# CANBus.net
KiCad netlist of a schematic drawn in Altium Designer
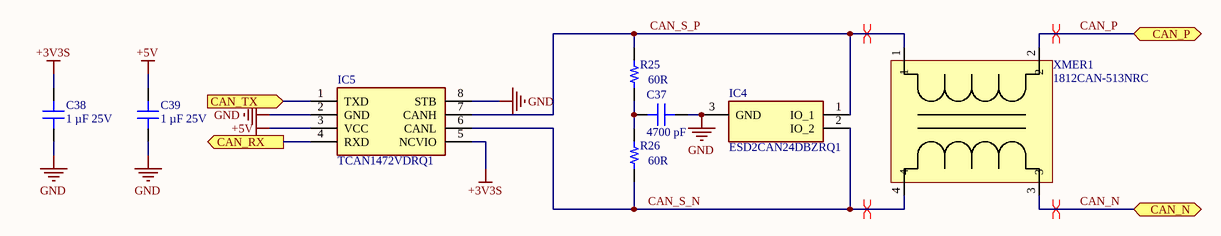
[diagram p0: CANBus.SchDoc]

(export (version "E")
  (design (tool "Eeschema 10.0.6"))
  (components
    (comp (ref "C37")
      (value "4700 pF")
      (footprint "CAP 0603_1608")
      (description "CAP CER 0603 4.7NF 16V X7R 10%")
      (fields (field (name "PART NUMBER") "C0603C472K4RECAUTO") (field (name "MANUFACTURER") "KEMET"))
      (libsource (lib "Celestial Altium Library - altium_library") (part "Capacitor"))
    )
    (comp (ref "C38")
      (value "1 µF")
      (footprint "CAP 0402_1005")
      (description "CAP CER 1UF 10V X5R 0402")
      (fields
        (field (name "PART NUMBER") "LMK105BJ105KPLF")
        (field (name "CAPACITANCE") "1 µF 25V")
        (field (name "MANUFACTURER") "Taiyo Yuden")
      )
      (libsource (lib "Celestial Altium Library - altium_library") (part "Capacitor"))
    )
    (comp (ref "C39")
      (value "1 µF")
      (footprint "CAP 0402_1005")
      (description "CAP CER 1UF 10V X5R 0402")
      (fields
        (field (name "PART NUMBER") "LMK105BJ105KPLF")
        (field (name "CAPACITANCE") "1 µF 25V")
        (field (name "MANUFACTURER") "Taiyo Yuden")
      )
      (libsource (lib "Celestial Altium Library - altium_library") (part "Capacitor"))
    )
    (comp (ref "IC4")
      (value "ESD2CAN24DBZRQ1")
      (footprint "PcbLib1:SOT95P237X112-3N")
      (description "Integrated Circuit")
      (fields (field (name "MOUSER PART NUMBER") "595-ESD2CAN24DBZRQ1"))
      (libsource (lib "Schlib1") (part "ESD2CAN24DBZRQ1"))
    )
    (comp (ref "IC5")
      (value "TCAN1472VDRQ1")
      (footprint "PcbLib1:SOIC127P600X175-8N")
      (description "Integrated Circuit")
      (fields (field (name "MOUSER PART NUMBER") "595-TCAN1472VDRQ1"))
      (libsource (lib "*") (part "TCAN1472VDRQ1"))
    )
    (comp (ref "R25")
      (value "60R")
      (footprint "RES 0603_1608")
      (description "RES 560 OHM 5% 1/10W 0603")
      (fields
        (field (name "PART NUMBER") "RMCF0603JT560R")
        (field (name "MANUFACTURER") "Stackpole Electronics Inc")
      )
      (libsource (lib "Celestial Altium Library - altium_library") (part "Resistor"))
    )
    (comp (ref "R26")
      (value "60R")
      (footprint "RES 0603_1608")
      (description "RES 560 OHM 5% 1/10W 0603")
      (fields
        (field (name "PART NUMBER") "RMCF0603JT560R")
        (field (name "MANUFACTURER") "Stackpole Electronics Inc")
      )
      (libsource (lib "Celestial Altium Library - altium_library") (part "Resistor"))
    )
    (comp (ref "XMER1")
      (value "1812CAN-513NRC")
      (footprint "XMER_1812CAN-513NRC_COC")
      (description "No Description Available")
      (libsource (lib "project_symbols") (part "1812CAN-513NRC"))
    )
  )
  (nets
    (net (code "1") (name "+3V3S") (class "Default")
      (node (ref "C38") (pin "2") (pinfunction "2_2") (pintype "passive"))
      (node (ref "IC5") (pin "5") (pinfunction "NCVIO_5") (pintype "passive"))
    )
    (net (code "2") (name "+5V") (class "Default")
      (node (ref "C39") (pin "2") (pinfunction "2_2") (pintype "passive"))
      (node (ref "IC5") (pin "3") (pinfunction "VCC_3") (pintype "passive"))
    )
    (net (code "3") (name "/CAN_N") (class "Default")
      (node (ref "XMER1") (pin "3") (pinfunction "3_3") (pintype "passive"))
    )
    (net (code "4") (name "/CAN_P") (class "Default")
      (node (ref "XMER1") (pin "2") (pinfunction "2_2") (pintype "passive"))
    )
    (net (code "5") (name "/CAN_RX") (class "Default")
      (node (ref "IC5") (pin "4") (pinfunction "RXD_4") (pintype "passive"))
    )
    (net (code "6") (name "/CAN_S_N") (class "Default")
      (node (ref "IC4") (pin "2") (pinfunction "IO_2_2") (pintype "passive"))
      (node (ref "IC5") (pin "6") (pinfunction "CANL_6") (pintype "passive"))
      (node (ref "R26") (pin "1") (pinfunction "1_1") (pintype "passive"))
      (node (ref "XMER1") (pin "4") (pinfunction "4_4") (pintype "passive"))
    )
    (net (code "7") (name "/CAN_S_P") (class "Default")
      (node (ref "IC4") (pin "1") (pinfunction "IO_1_1") (pintype "passive"))
      (node (ref "IC5") (pin "7") (pinfunction "CANH_7") (pintype "passive"))
      (node (ref "R25") (pin "2") (pinfunction "2_2") (pintype "passive"))
      (node (ref "XMER1") (pin "1") (pinfunction "1_1") (pintype "passive"))
    )
    (net (code "8") (name "/CAN_TX") (class "Default")
      (node (ref "IC5") (pin "1") (pinfunction "TXD_1") (pintype "passive"))
    )
    (net (code "9") (name "GND") (class "Default")
      (node (ref "C37") (pin "2") (pinfunction "2_2") (pintype "passive"))
      (node (ref "C38") (pin "1") (pinfunction "1_1") (pintype "passive"))
      (node (ref "C39") (pin "1") (pinfunction "1_1") (pintype "passive"))
      (node (ref "IC4") (pin "3") (pinfunction "GND_3") (pintype "passive"))
      (node (ref "IC5") (pin "2") (pinfunction "GND_2") (pintype "passive"))
      (node (ref "IC5") (pin "8") (pinfunction "STB_8") (pintype "passive"))
    )
    (net (code "10") (name "Net-(C37-Pad1)") (class "Default")
      (node (ref "C37") (pin "1") (pinfunction "1_1") (pintype "passive"))
      (node (ref "R25") (pin "1") (pinfunction "1_1") (pintype "passive"))
      (node (ref "R26") (pin "2") (pinfunction "2_2") (pintype "passive"))
    )
  )
)
